# USB.net
KiCad netlist of a schematic drawn in Altium Designer
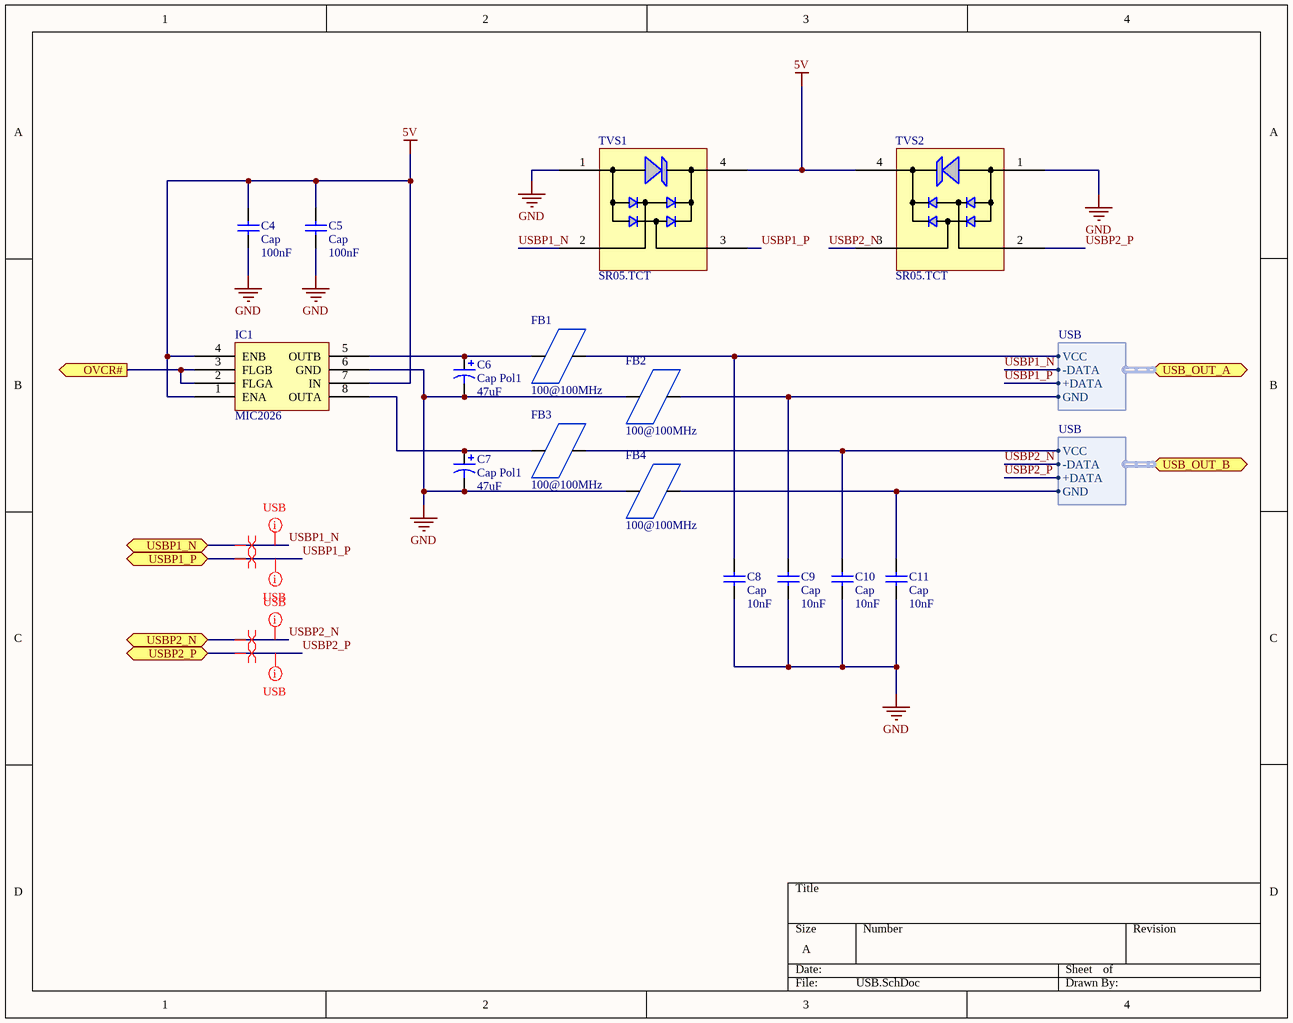
[diagram p0: USB.SchDoc]

(export (version "E")
  (design (tool "Eeschema 10.0.6"))
  (components
    (comp (ref "C4")
      (value "Cap")
      (footprint "0603")
      (description "Capacitor")
      (fields (field (name "ALTIUM_VALUE") "100nF") (field (name "PUBLISHER") "Altium Limited"))
      (libsource (lib "Miscellaneous Devices") (part "Cap"))
    )
    (comp (ref "C5")
      (value "Cap")
      (footprint "0603")
      (description "Capacitor")
      (fields (field (name "ALTIUM_VALUE") "100nF") (field (name "PUBLISHER") "Altium Limited"))
      (libsource (lib "Miscellaneous Devices") (part "Cap"))
    )
    (comp (ref "C6")
      (value "Cap Pol1")
      (footprint "CAPPR5-5x5")
      (description "Polarized Capacitor (Radial)")
      (fields (field (name "ALTIUM_VALUE") "47uF") (field (name "PUBLISHER") "Altium Limited"))
      (libsource (lib "Miscellaneous Devices") (part "Cap Pol1"))
    )
    (comp (ref "C7")
      (value "Cap Pol1")
      (footprint "CAPPR5-5x5")
      (description "Polarized Capacitor (Radial)")
      (fields (field (name "ALTIUM_VALUE") "47uF") (field (name "PUBLISHER") "Altium Limited"))
      (libsource (lib "Miscellaneous Devices") (part "Cap Pol1"))
    )
    (comp (ref "C8")
      (value "Cap")
      (footprint "0603")
      (description "Capacitor")
      (fields (field (name "ALTIUM_VALUE") "10nF") (field (name "PUBLISHER") "Altium Limited"))
      (libsource (lib "Miscellaneous Devices") (part "Cap"))
    )
    (comp (ref "C9")
      (value "Cap")
      (footprint "0603")
      (description "Capacitor")
      (fields (field (name "ALTIUM_VALUE") "10nF") (field (name "PUBLISHER") "Altium Limited"))
      (libsource (lib "Miscellaneous Devices") (part "Cap"))
    )
    (comp (ref "C10")
      (value "Cap")
      (footprint "0603")
      (description "Capacitor")
      (fields (field (name "ALTIUM_VALUE") "10nF") (field (name "PUBLISHER") "Altium Limited"))
      (libsource (lib "Miscellaneous Devices") (part "Cap"))
    )
    (comp (ref "C11")
      (value "Cap")
      (footprint "0603")
      (description "Capacitor")
      (fields (field (name "ALTIUM_VALUE") "10nF") (field (name "PUBLISHER") "Altium Limited"))
      (libsource (lib "Miscellaneous Devices") (part "Cap"))
    )
    (comp (ref "FB1")
      (value "100@100MHz")
      (footprint "INDC1608X09N")
      (description "Ferrite Bead")
      (libsource (lib "BKP1608 - Ferrite Bead") (part "Ferrite Bead"))
    )
    (comp (ref "FB2")
      (value "100@100MHz")
      (footprint "INDC1608X09N")
      (description "Ferrite Bead")
      (libsource (lib "BKP1608 - Ferrite Bead") (part "Ferrite Bead"))
    )
    (comp (ref "FB3")
      (value "100@100MHz")
      (footprint "INDC1608X09N")
      (libsource (lib "BKP1608 - Ferrite Bead") (part "Ferrite Bead"))
    )
    (comp (ref "FB4")
      (value "100@100MHz")
      (footprint "INDC1608X09N")
      (description "Ferrite Bead")
      (libsource (lib "BKP1608 - Ferrite Bead") (part "Ferrite Bead"))
    )
    (comp (ref "IC1")
      (value "MIC2026")
      (footprint "8-Pin SOIC")
      (description "Micrel MIC2026 Dual-Channel Power Distribution Switch")
      (libsource (lib "MIC2026") (part "MIC2026"))
    )
    (comp (ref "TVS1")
      (value "SR05.TCT")
      (footprint "SOT143")
      (description "IC TVS ARRAY 2-LINE 5V SOT-143")
      (libsource (lib "TVS Arrays") (part "SR05.TCT"))
    )
    (comp (ref "TVS2")
      (value "SR05.TCT")
      (footprint "SOT143")
      (description "IC TVS ARRAY 2-LINE 5V SOT-143")
      (libsource (lib "") (part "SR05.TCT_1"))
    )
  )
  (nets
    (net (code "2") (name "/OVCR#") (class "Default")
      (node (ref "IC1") (pin "2") (pinfunction "FLGA_2") (pintype "passive"))
      (node (ref "IC1") (pin "3") (pinfunction "FLGB_3") (pintype "passive"))
    )
    (net (code "3") (name "/USBP1_N") (class "Default")
      (node (ref "TVS1") (pin "2") (pinfunction "2_2") (pintype "passive"))
    )
    (net (code "4") (name "/USBP1_P") (class "Default")
      (node (ref "TVS1") (pin "3") (pinfunction "3_3") (pintype "passive"))
    )
    (net (code "5") (name "/USBP2_N") (class "Default")
      (node (ref "TVS2") (pin "3") (pinfunction "3_3") (pintype "passive"))
    )
    (net (code "6") (name "/USBP2_P") (class "Default")
      (node (ref "TVS2") (pin "2") (pinfunction "2_2") (pintype "passive"))
    )
    (net (code "8") (name "5V") (class "Default")
      (node (ref "C4") (pin "2") (pinfunction "2_2") (pintype "passive"))
      (node (ref "C5") (pin "2") (pinfunction "2_2") (pintype "passive"))
      (node (ref "IC1") (pin "1") (pinfunction "ENA_1") (pintype "passive"))
      (node (ref "IC1") (pin "4") (pinfunction "ENB_4") (pintype "passive"))
      (node (ref "IC1") (pin "7") (pinfunction "IN_7") (pintype "passive"))
      (node (ref "TVS1") (pin "4") (pinfunction "4_4") (pintype "passive"))
      (node (ref "TVS2") (pin "4") (pinfunction "4_4") (pintype "passive"))
    )
    (net (code "9") (name "GND") (class "Default")
      (node (ref "C10") (pin "1") (pinfunction "1_1") (pintype "passive"))
      (node (ref "C11") (pin "1") (pinfunction "1_1") (pintype "passive"))
      (node (ref "C4") (pin "1") (pinfunction "1_1") (pintype "passive"))
      (node (ref "C5") (pin "1") (pinfunction "1_1") (pintype "passive"))
      (node (ref "C6") (pin "2") (pinfunction "2_2") (pintype "passive"))
      (node (ref "C7") (pin "2") (pinfunction "2_2") (pintype "passive"))
      (node (ref "C8") (pin "1") (pinfunction "1_1") (pintype "passive"))
      (node (ref "C9") (pin "1") (pinfunction "1_1") (pintype "passive"))
      (node (ref "FB2") (pin "1") (pinfunction "1_1") (pintype "passive"))
      (node (ref "FB4") (pin "1") (pinfunction "1_1") (pintype "passive"))
      (node (ref "IC1") (pin "6") (pinfunction "GND_6") (pintype "passive"))
      (node (ref "TVS1") (pin "1") (pinfunction "1_1") (pintype "passive"))
      (node (ref "TVS2") (pin "1") (pinfunction "1_1") (pintype "passive"))
    )
    (net (code "10") (name "Net-(C8-Pad2)") (class "Default")
      (node (ref "C8") (pin "2") (pinfunction "2_2") (pintype "passive"))
      (node (ref "FB1") (pin "2") (pinfunction "2_2") (pintype "passive"))
    )
    (net (code "11") (name "Net-(C9-Pad2)") (class "Default")
      (node (ref "C9") (pin "2") (pinfunction "2_2") (pintype "passive"))
      (node (ref "FB2") (pin "2") (pinfunction "2_2") (pintype "passive"))
    )
    (net (code "12") (name "Net-(C10-Pad2)") (class "Default")
      (node (ref "C10") (pin "2") (pinfunction "2_2") (pintype "passive"))
      (node (ref "FB3") (pin "2") (pinfunction "2_2") (pintype "passive"))
    )
    (net (code "13") (name "Net-(C11-Pad2)") (class "Default")
      (node (ref "C11") (pin "2") (pinfunction "2_2") (pintype "passive"))
      (node (ref "FB4") (pin "2") (pinfunction "2_2") (pintype "passive"))
    )
    (net (code "14") (name "Net-(IC1-OUTA)") (class "Default")
      (node (ref "C7") (pin "1") (pinfunction "1_1") (pintype "passive"))
      (node (ref "FB3") (pin "1") (pinfunction "1_1") (pintype "passive"))
      (node (ref "IC1") (pin "8") (pinfunction "OUTA_8") (pintype "passive"))
    )
    (net (code "15") (name "Net-(IC1-OUTB)") (class "Default")
      (node (ref "C6") (pin "1") (pinfunction "1_1") (pintype "passive"))
      (node (ref "FB1") (pin "1") (pinfunction "1_1") (pintype "passive"))
      (node (ref "IC1") (pin "5") (pinfunction "OUTB_5") (pintype "passive"))
    )
  )
)
